# USB-C_to_ESP.net
KiCad netlist of a schematic drawn in Altium Designer
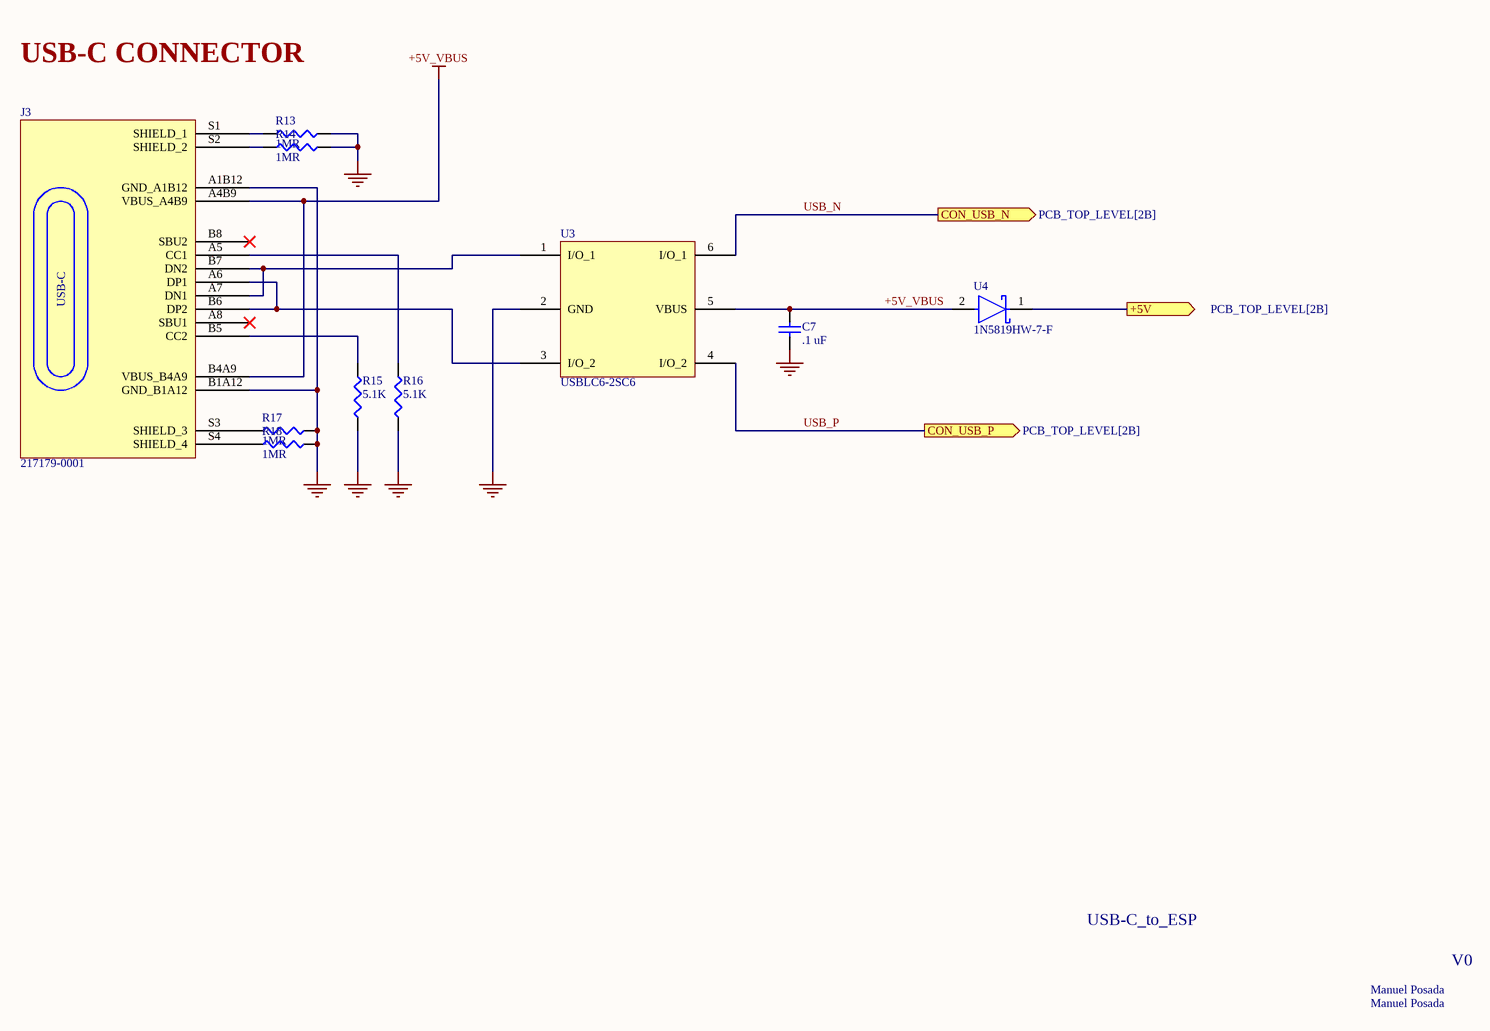
[diagram p0: USB-C_to_ESP.SchDoc]

(export (version "E")
  (design (tool "Eeschema 10.0.6"))
  (components
    (comp (ref "C7")
      (value ".1 uF")
      (footprint "CAP_CL21_SAM-L")
      (description "50V 100nF X7R ±10% 0805 Multilayer Ceramic Capacitors MLCC - SMD/SMT ROHS")
      (fields
        (field (name "MANUFACTURER") "Samsung Electro-Mechanics")
        (field (name "MANUFACTURER PART NUMBER") "CL21B104KBCNNNC")
      )
      (libsource (lib "Schlib") (part "CL21B104KBCNNNC"))
    )
    (comp (ref "J3")
      (value "217179-0001")
      (footprint "FP-2171790001-MFG")
      (description "CONN RCP USB2.0 TYP C 24P SMD RA")
      (fields (field (name "MANUFACTURER") "Molex") (field (name "LCSC PART NUMBER") "C3197684"))
      (libsource (lib "Schlib") (part "217179-0001"))
    )
    (comp (ref "R13")
      (value "1MR")
      (footprint "RES_1220_SUS-L")
      (description "Res Thin Film 0805 1M Ohm 0.1% 0.125W(1/8W) ±25ppm/C Sulfur Resistant Pad SMD Automotive T/R")
      (fields
        (field (name "MANUFACTURER") "Susumu")
        (field (name "MANUFACTURER PART NUMBER") "RG2012P-105-B-T5")
      )
      (libsource (lib "Schlib") (part "RG2012P-105-B-T5"))
    )
    (comp (ref "R14")
      (value "1MR")
      (footprint "RES_1220_SUS-L")
      (description "Res Thin Film 0805 1M Ohm 0.1% 0.125W(1/8W) ±25ppm/C Sulfur Resistant Pad SMD Automotive T/R")
      (fields
        (field (name "MANUFACTURER") "Susumu")
        (field (name "MANUFACTURER PART NUMBER") "RG2012P-105-B-T5")
      )
      (libsource (lib "Schlib") (part "RG2012P-105-B-T5"))
    )
    (comp (ref "R15")
      (value "5.1K")
      (footprint "RES_1220_SUS-L")
      (description "Res Thin Film 0805 5.1K Ohm 0.1% 0.125W(1/8W) ±25ppm/C Sulfur Resistant Pad SMD Automotive T/R")
      (fields
        (field (name "MANUFACTURER") "Susumu")
        (field (name "MANUFACTURER PART NUMBER") "RG2012P-512-B-T5")
      )
      (libsource (lib "Schlib") (part "RG2012P-512-B-T5"))
    )
    (comp (ref "R16")
      (value "5.1K")
      (footprint "RES_1220_SUS-L")
      (description "Res Thin Film 0805 5.1K Ohm 0.1% 0.125W(1/8W) ±25ppm/C Sulfur Resistant Pad SMD Automotive T/R")
      (fields
        (field (name "MANUFACTURER") "Susumu")
        (field (name "MANUFACTURER PART NUMBER") "RG2012P-512-B-T5")
      )
      (libsource (lib "Schlib") (part "RG2012P-512-B-T5"))
    )
    (comp (ref "R17")
      (value "1MR")
      (footprint "RES_1220_SUS-L")
      (description "Res Thin Film 0805 1M Ohm 0.1% 0.125W(1/8W) ±25ppm/C Sulfur Resistant Pad SMD Automotive T/R")
      (fields
        (field (name "MANUFACTURER") "Susumu")
        (field (name "MANUFACTURER PART NUMBER") "RG2012P-105-B-T5")
      )
      (libsource (lib "Schlib") (part "RG2012P-105-B-T5"))
    )
    (comp (ref "R18")
      (value "1MR")
      (footprint "RES_1220_SUS-L")
      (description "Res Thin Film 0805 1M Ohm 0.1% 0.125W(1/8W) ±25ppm/C Sulfur Resistant Pad SMD Automotive T/R")
      (fields
        (field (name "MANUFACTURER") "Susumu")
        (field (name "MANUFACTURER PART NUMBER") "RG2012P-105-B-T5")
      )
      (libsource (lib "Schlib") (part "RG2012P-105-B-T5"))
    )
    (comp (ref "U3")
      (value "USBLC6-2SC6")
      (footprint "SOT23-6L_STM")
      (description "17V Clamp 5A (8/20µs) Ipp Tvs Diode Surface Mount SOT-23-6")
      (fields (field (name "MANUFACTURER") "STMicroelectronics"))
      (libsource (lib "Schlib") (part "USBLC6-2SC6"))
    )
    (comp (ref "U4")
      (value "1N5819HW-7-F")
      (footprint "FP-SOD123-IPC_B")
      (description "DIODE SCHOTTKY 40V 1A SOD123")
      (fields (field (name "MANUFACTURER") "Diodes Inc."))
      (libsource (lib "Schlib") (part "1N5819HW-7-F"))
    )
  )
  (nets
    (net (code "1") (name "+5V_VBUS") (class "Default")
      (node (ref "C7") (pin "2") (pinfunction "2_2") (pintype "passive"))
      (node (ref "J3") (pin "A4B9") (pinfunction "VBUS_A4B9_A4B9") (pintype "passive"))
      (node (ref "J3") (pin "B4A9") (pinfunction "VBUS_B4A9_B4A9") (pintype "passive"))
      (node (ref "U3") (pin "5") (pinfunction "VBUS_5") (pintype "passive"))
      (node (ref "U4") (pin "2") (pinfunction "A_2") (pintype "passive"))
    )
    (net (code "2") (name "/+5V") (class "Default")
      (node (ref "U4") (pin "1") (pinfunction "C_1") (pintype "passive"))
    )
    (net (code "3") (name "/USB_N") (class "Default")
      (node (ref "U3") (pin "6") (pinfunction "I/O_1_6") (pintype "passive"))
    )
    (net (code "4") (name "/USB_P") (class "Default")
      (node (ref "U3") (pin "4") (pinfunction "I/O_2_4") (pintype "passive"))
    )
    (net (code "5") (name "GND") (class "Default")
      (node (ref "C7") (pin "1") (pinfunction "1_1") (pintype "passive"))
      (node (ref "J3") (pin "A1B12") (pinfunction "GND_A1B12_A1B12") (pintype "passive"))
      (node (ref "J3") (pin "B1A12") (pinfunction "GND_B1A12_B1A12") (pintype "passive"))
      (node (ref "R13") (pin "2") (pinfunction "2_2") (pintype "passive"))
      (node (ref "R14") (pin "2") (pinfunction "2_2") (pintype "passive"))
      (node (ref "R15") (pin "1") (pinfunction "1_1") (pintype "passive"))
      (node (ref "R16") (pin "1") (pinfunction "1_1") (pintype "passive"))
      (node (ref "R17") (pin "2") (pinfunction "2_2") (pintype "passive"))
      (node (ref "R18") (pin "2") (pinfunction "2_2") (pintype "passive"))
      (node (ref "U3") (pin "2") (pinfunction "GND_2") (pintype "passive"))
    )
    (net (code "6") (name "Net-(J3-CC1)") (class "Default")
      (node (ref "J3") (pin "A5") (pinfunction "CC1_A5") (pintype "passive"))
      (node (ref "R16") (pin "2") (pinfunction "2_2") (pintype "passive"))
    )
    (net (code "7") (name "Net-(J3-CC2)") (class "Default")
      (node (ref "J3") (pin "B5") (pinfunction "CC2_B5") (pintype "passive"))
      (node (ref "R15") (pin "2") (pinfunction "2_2") (pintype "passive"))
    )
    (net (code "8") (name "Net-(J3-DN1)") (class "Default")
      (node (ref "J3") (pin "A7") (pinfunction "DN1_A7") (pintype "passive"))
      (node (ref "J3") (pin "B7") (pinfunction "DN2_B7") (pintype "passive"))
      (node (ref "U3") (pin "1") (pinfunction "I/O_1_1") (pintype "passive"))
    )
    (net (code "9") (name "Net-(J3-DP1)") (class "Default")
      (node (ref "J3") (pin "A6") (pinfunction "DP1_A6") (pintype "passive"))
      (node (ref "J3") (pin "B6") (pinfunction "DP2_B6") (pintype "passive"))
      (node (ref "U3") (pin "3") (pinfunction "I/O_2_3") (pintype "passive"))
    )
    (net (code "10") (name "Net-(J3-SHIELD_1)") (class "Default")
      (node (ref "J3") (pin "S1") (pinfunction "SHIELD_1_S1") (pintype "passive"))
      (node (ref "R13") (pin "1") (pinfunction "1_1") (pintype "passive"))
    )
    (net (code "11") (name "Net-(J3-SHIELD_2)") (class "Default")
      (node (ref "J3") (pin "S2") (pinfunction "SHIELD_2_S2") (pintype "passive"))
      (node (ref "R14") (pin "1") (pinfunction "1_1") (pintype "passive"))
    )
    (net (code "12") (name "Net-(J3-SHIELD_3)") (class "Default")
      (node (ref "J3") (pin "S3") (pinfunction "SHIELD_3_S3") (pintype "passive"))
      (node (ref "R17") (pin "1") (pinfunction "1_1") (pintype "passive"))
    )
    (net (code "13") (name "Net-(J3-SHIELD_4)") (class "Default")
      (node (ref "J3") (pin "S4") (pinfunction "SHIELD_4_S4") (pintype "passive"))
      (node (ref "R18") (pin "1") (pinfunction "1_1") (pintype "passive"))
    )
    (net (code "14") (name "unconnected-(J3-SBU1-PadA8)") (class "Default")
      (node (ref "J3") (pin "A8") (pinfunction "SBU1_A8") (pintype "passive+no_connect"))
    )
    (net (code "15") (name "unconnected-(J3-SBU2-PadB8)") (class "Default")
      (node (ref "J3") (pin "B8") (pinfunction "SBU2_B8") (pintype "passive+no_connect"))
    )
  )
)
